# Water_Counter_Nathan_Amir.net
KiCad netlist of a schematic drawn in EasyEDA
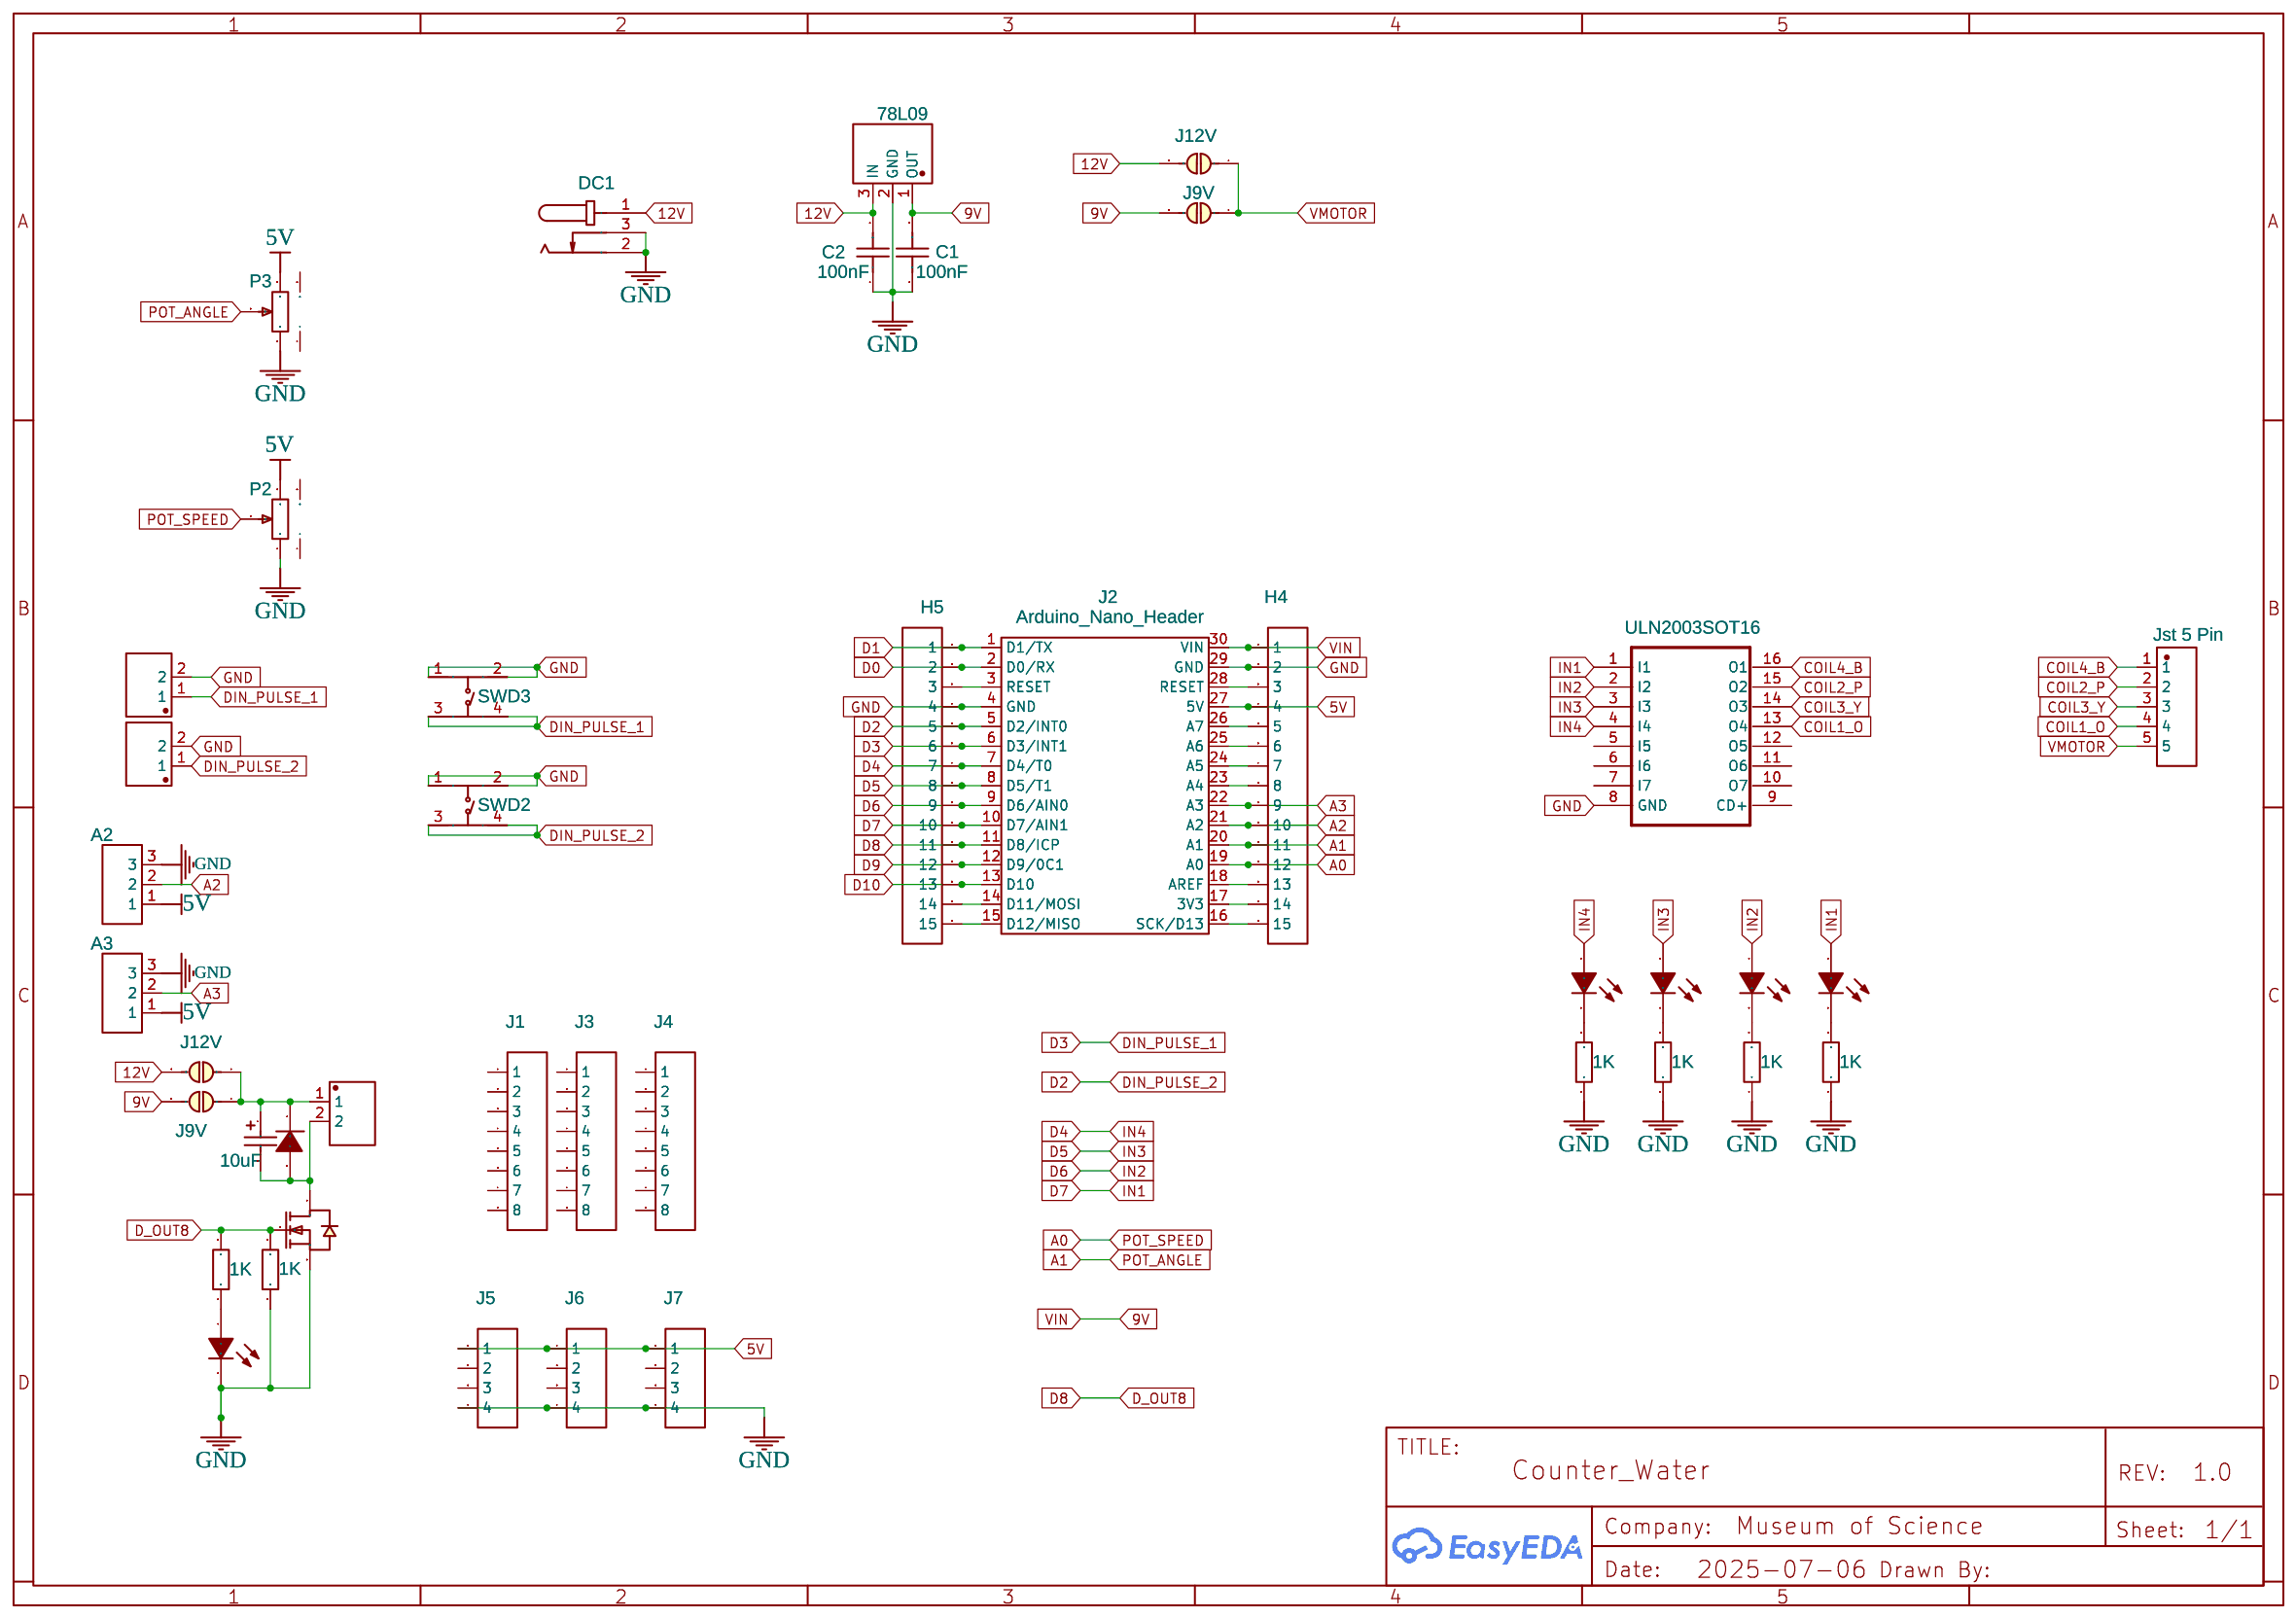
[diagram p0: schematic sheet]

(export (version "E")
  (design (tool "Eeschema 10.0.6"))
  (components
    (comp (ref "A2") (value "FK2510") (libsource (lib "") (part "kf2510_3A")))
    (comp (ref "A3") (value "FK2510") (libsource (lib "") (part "kf2510_3A")))
    (comp (ref "C1") (value "100nF") (libsource (lib "") (part "CC0603KRX7R9BB104")))
    (comp (ref "C2") (value "100nF") (libsource (lib "") (part "CC0603KRX7R9BB104")))
    (comp (ref "D2")
      (value "KF2510-2A")
      (fields (field (name "Manufacturer") "BOOMELE"))
      (libsource (lib "") (part "KF2510-2A"))
    )
    (comp (ref "D3")
      (value "KF2510-2A")
      (fields (field (name "Manufacturer") "BOOMELE"))
      (libsource (lib "") (part "KF2510-2A"))
    )
    (comp (ref "DC1")
      (value "DC")
      (fields (field (name "Manufacturer Part") "DC005-2.0MM") (field (name "Manufacturer") "SOFNG"))
      (libsource (lib "") (part "DC005-2.0MM"))
    )
    (comp (ref "ECM1") (value "10uF") (libsource (lib "") (part "TAJA106K016RNJ")))
    (comp (ref "ECON1")
      (value "D_OUT8")
      (fields (field (name "Manufacturer Part") "KF2510-2A") (field (name "Manufacturer") "BOOMELE"))
      (libsource (lib "") (part "KF2510-2A_1"))
    )
    (comp (ref "EDM1")
      (value "1N4007")
      (fields (field (name "Manufacturer Part") "1N4007F") (field (name "Manufacturer") "SK"))
      (libsource (lib "") (part "1N4007F"))
    )
    (comp (ref "ELD1")
      (value "LED")
      (fields
        (field (name "Manufacturer Part") "19-217/BHC-ZL1M2RY/3T")
        (field (name "Manufacturer") "EVERLIGHT")
      )
      (libsource (lib "") (part "19-217/BHC-ZL1M2RY/3T"))
    )
    (comp (ref "ELD2")
      (value "LED")
      (fields
        (field (name "Manufacturer Part") "19-217/BHC-ZL1M2RY/3T")
        (field (name "Manufacturer") "EVERLIGHT")
      )
      (libsource (lib "") (part "19-217/BHC-ZL1M2RY/3T"))
    )
    (comp (ref "ELD3")
      (value "LED")
      (fields
        (field (name "Manufacturer Part") "19-217/BHC-ZL1M2RY/3T")
        (field (name "Manufacturer") "EVERLIGHT")
      )
      (libsource (lib "") (part "19-217/BHC-ZL1M2RY/3T"))
    )
    (comp (ref "ELD4")
      (value "LED")
      (fields
        (field (name "Manufacturer Part") "19-217/BHC-ZL1M2RY/3T")
        (field (name "Manufacturer") "EVERLIGHT")
      )
      (libsource (lib "") (part "19-217/BHC-ZL1M2RY/3T"))
    )
    (comp (ref "ELD5")
      (value "LED")
      (fields
        (field (name "Manufacturer Part") "19-217/BHC-ZL1M2RY/3T")
        (field (name "Manufacturer") "EVERLIGHT")
      )
      (libsource (lib "") (part "19-217/BHC-ZL1M2RY/3T"))
    )
    (comp (ref "EQ1")
      (value "Q")
      (fields (field (name "Manufacturer Part") "AO3400") (field (name "Manufacturer") "ElecSuper(静芯微）"))
      (libsource (lib "") (part "JSM2302"))
    )
    (comp (ref "ERG1")
      (value "1K")
      (fields (field (name "Manufacturer Part") "0603WAF1001T5E") (field (name "Manufacturer") "UniOhm"))
      (libsource (lib "") (part "0603WAF1001T5E_1"))
    )
    (comp (ref "ERL1")
      (value "1K")
      (fields (field (name "Manufacturer Part") "0603WAF1001T5E") (field (name "Manufacturer") "UniOhm"))
      (libsource (lib "") (part "0603WAF1001T5E"))
    )
    (comp (ref "ERL2")
      (value "1K")
      (fields (field (name "Manufacturer Part") "0603WAF1001T5E") (field (name "Manufacturer") "UniOhm"))
      (libsource (lib "") (part "0603WAF1001T5E"))
    )
    (comp (ref "ERL3")
      (value "1K")
      (fields (field (name "Manufacturer Part") "0603WAF1001T5E") (field (name "Manufacturer") "UniOhm"))
      (libsource (lib "") (part "0603WAF1001T5E"))
    )
    (comp (ref "ERL4")
      (value "1K")
      (fields (field (name "Manufacturer Part") "0603WAF1001T5E") (field (name "Manufacturer") "UniOhm"))
      (libsource (lib "") (part "0603WAF1001T5E"))
    )
    (comp (ref "ERL5")
      (value "1K")
      (fields (field (name "Manufacturer Part") "0603WAF1001T5E") (field (name "Manufacturer") "UniOhm"))
      (libsource (lib "") (part "0603WAF1001T5E"))
    )
    (comp (ref "H4") (value "HDR-F-2.54_1x15") (libsource (lib "") (part "HDR-F-2.54_1x15_1")))
    (comp (ref "H5") (value "HDR-F-2.54_1x15") (libsource (lib "") (part "HDR-F-2.54_1x15")))
    (comp (ref "IC1") (value "ULN2003SOT16") (libsource (lib "") (part "ULN2003SOT16")))
    (comp (ref "J1")
      (value "HDR-M-2.54_1x8")
      (fields (field (name "BOM_Supplier Part") "C190820"))
      (libsource (lib "") (part "HDR-M-2.54_1x8"))
    )
    (comp (ref "J2") (value "Arduino_Nano_Header") (libsource (lib "") (part "Arduino_Nano_Header")))
    (comp (ref "J3")
      (value "HDR-M-2.54_1x8")
      (fields (field (name "BOM_Supplier Part") "C190820"))
      (libsource (lib "") (part "HDR-M-2.54_1x8"))
    )
    (comp (ref "J4")
      (value "HDR-M-2.54_1x8")
      (fields (field (name "BOM_Supplier Part") "C190820"))
      (libsource (lib "") (part "HDR-M-2.54_1x8"))
    )
    (comp (ref "J5")
      (value "HDR-M-2.54_1x4")
      (fields (field (name "BOM_Supplier Part") "C124378"))
      (libsource (lib "") (part "HDR-M-2.54_1x4"))
    )
    (comp (ref "J5V_2") (value "J9V") (libsource (lib "") (part "JUMPER-SMT_2")))
    (comp (ref "J6")
      (value "HDR-M-2.54_1x4")
      (fields (field (name "BOM_Supplier Part") "C124378"))
      (libsource (lib "") (part "HDR-M-2.54_1x4"))
    )
    (comp (ref "J7")
      (value "HDR-M-2.54_1x4")
      (fields (field (name "BOM_Supplier Part") "C124378"))
      (libsource (lib "") (part "HDR-M-2.54_1x4"))
    )
    (comp (ref "J9V_1") (value "J9V") (libsource (lib "") (part "JUMPER-SMT_2_2")))
    (comp (ref "J12V_1") (value "J12V") (libsource (lib "") (part "JUMPER-SMT_2_1")))
    (comp (ref "J12V_2") (value "J12V") (libsource (lib "") (part "JUMPER-SMT_2_1")))
    (comp (ref "P2") (value "长柄旋转电位器") (libsource (lib "") (part "长柄旋转电位器")))
    (comp (ref "P3") (value "长柄旋转电位器") (libsource (lib "") (part "长柄旋转电位器")))
    (comp (ref "SWD2")
      (value "TC-6610-7-160G")
      (fields (field (name "Manufacturer") "HCTL(华灿天禄)"))
      (libsource (lib "") (part "TC-6610-7-160G"))
    )
    (comp (ref "SWD3")
      (value "TC-6610-7-160G")
      (fields (field (name "Manufacturer") "HCTL(华灿天禄)"))
      (libsource (lib "") (part "TC-6610-7-160G"))
    )
    (comp (ref "U1")
      (value "78L09")
      (fields (field (name "Manufacturer") "CBI(创基)"))
      (libsource (lib "") (part "78L09U 78L09"))
    )
    (comp (ref "U2")
      (value "Jst 5 Pin")
      (fields (field (name "Manufacturer") "Vicky"))
      (libsource (lib "") (part "Jst 5 Pin"))
    )
  )
  (nets
    (net (code "1") (name "5V") (class "Default")
      (node (ref "A2") (pin "1") (pinfunction "1_1") (pintype "unspecified"))
      (node (ref "A3") (pin "1") (pinfunction "1_1") (pintype "unspecified"))
      (node (ref "H4") (pin "4") (pinfunction "4_4") (pintype "unspecified"))
      (node (ref "J2") (pin "27") (pinfunction "5V_27") (pintype "unspecified"))
      (node (ref "J5") (pin "1") (pinfunction "1_1") (pintype "unspecified"))
      (node (ref "J6") (pin "1") (pinfunction "1_1") (pintype "unspecified"))
      (node (ref "J7") (pin "1") (pinfunction "1_1") (pintype "unspecified"))
      (node (ref "P2") (pin "3") (pinfunction "3_3") (pintype "input"))
      (node (ref "P3") (pin "3") (pinfunction "3_3") (pintype "input"))
    )
    (net (code "2") (name "9V") (class "Default")
      (node (ref "C1") (pin "2") (pinfunction "2_2") (pintype "unspecified"))
      (node (ref "H4") (pin "1") (pinfunction "1_1") (pintype "unspecified"))
      (node (ref "J2") (pin "30") (pinfunction "VIN_30") (pintype "unspecified"))
      (node (ref "J5V_2") (pin "2") (pinfunction "2_2") (pintype "bidirectional"))
      (node (ref "J9V_1") (pin "2") (pinfunction "2_2") (pintype "bidirectional"))
      (node (ref "U1") (pin "1") (pinfunction "OUT_1") (pintype "unspecified"))
    )
    (net (code "3") (name "12V") (class "Default")
      (node (ref "C2") (pin "2") (pinfunction "2_2") (pintype "unspecified"))
      (node (ref "DC1") (pin "1") (pinfunction "1_1") (pintype "unspecified"))
      (node (ref "J12V_1") (pin "2") (pinfunction "2_2") (pintype "bidirectional"))
      (node (ref "J12V_2") (pin "2") (pinfunction "2_2") (pintype "bidirectional"))
      (node (ref "U1") (pin "3") (pinfunction "IN_3") (pintype "unspecified"))
    )
    (net (code "4") (name "A0") (class "Default")
      (node (ref "H4") (pin "12") (pinfunction "12_12") (pintype "unspecified"))
      (node (ref "J2") (pin "19") (pinfunction "A0_19") (pintype "unspecified"))
      (node (ref "P2") (pin "2") (pinfunction "2_2") (pintype "input"))
    )
    (net (code "5") (name "A1") (class "Default")
      (node (ref "H4") (pin "11") (pinfunction "11_11") (pintype "unspecified"))
      (node (ref "J2") (pin "20") (pinfunction "A1_20") (pintype "unspecified"))
      (node (ref "P3") (pin "2") (pinfunction "2_2") (pintype "input"))
    )
    (net (code "6") (name "A2") (class "Default")
      (node (ref "A2") (pin "2") (pinfunction "2_2") (pintype "unspecified"))
      (node (ref "H4") (pin "10") (pinfunction "10_10") (pintype "unspecified"))
      (node (ref "J2") (pin "21") (pinfunction "A2_21") (pintype "unspecified"))
    )
    (net (code "7") (name "A3") (class "Default")
      (node (ref "A3") (pin "2") (pinfunction "2_2") (pintype "unspecified"))
      (node (ref "H4") (pin "9") (pinfunction "9_9") (pintype "unspecified"))
      (node (ref "J2") (pin "22") (pinfunction "A3_22") (pintype "unspecified"))
    )
    (net (code "8") (name "COIL1_O") (class "Default")
      (node (ref "IC1") (pin "13") (pinfunction "O4_13") (pintype "bidirectional"))
      (node (ref "U2") (pin "4") (pinfunction "4_4") (pintype "unspecified"))
    )
    (net (code "9") (name "COIL2_P") (class "Default")
      (node (ref "IC1") (pin "15") (pinfunction "O2_15") (pintype "bidirectional"))
      (node (ref "U2") (pin "2") (pinfunction "2_2") (pintype "unspecified"))
    )
    (net (code "10") (name "COIL3_Y") (class "Default")
      (node (ref "IC1") (pin "14") (pinfunction "O3_14") (pintype "bidirectional"))
      (node (ref "U2") (pin "3") (pinfunction "3_3") (pintype "unspecified"))
    )
    (net (code "11") (name "COIL4_B") (class "Default")
      (node (ref "IC1") (pin "16") (pinfunction "O1_16") (pintype "bidirectional"))
      (node (ref "U2") (pin "1") (pinfunction "1_1") (pintype "unspecified"))
    )
    (net (code "12") (name "D0") (class "Default")
      (node (ref "H5") (pin "2") (pinfunction "2_2") (pintype "unspecified"))
      (node (ref "J2") (pin "2") (pinfunction "D0/RX_2") (pintype "unspecified"))
    )
    (net (code "13") (name "D1") (class "Default")
      (node (ref "H5") (pin "1") (pinfunction "1_1") (pintype "unspecified"))
      (node (ref "J2") (pin "1") (pinfunction "D1/TX_1") (pintype "unspecified"))
    )
    (net (code "14") (name "D2") (class "Default")
      (node (ref "D2") (pin "1") (pinfunction "1_1") (pintype "unspecified"))
      (node (ref "H5") (pin "5") (pinfunction "5_5") (pintype "unspecified"))
      (node (ref "J2") (pin "5") (pinfunction "D2/INT0_5") (pintype "unspecified"))
      (node (ref "SWD2") (pin "3") (pinfunction "3_3") (pintype "unspecified"))
      (node (ref "SWD2") (pin "4") (pinfunction "4_4") (pintype "unspecified"))
    )
    (net (code "15") (name "D3") (class "Default")
      (node (ref "D3") (pin "1") (pinfunction "1_1") (pintype "unspecified"))
      (node (ref "H5") (pin "6") (pinfunction "6_6") (pintype "unspecified"))
      (node (ref "J2") (pin "6") (pinfunction "D3/INT1_6") (pintype "unspecified"))
      (node (ref "SWD3") (pin "3") (pinfunction "3_3") (pintype "unspecified"))
      (node (ref "SWD3") (pin "4") (pinfunction "4_4") (pintype "unspecified"))
    )
    (net (code "16") (name "D4") (class "Default")
      (node (ref "ELD1") (pin "1") (pinfunction "A_1") (pintype "input"))
      (node (ref "H5") (pin "7") (pinfunction "7_7") (pintype "unspecified"))
      (node (ref "IC1") (pin "4") (pinfunction "I4_4") (pintype "bidirectional"))
      (node (ref "J2") (pin "7") (pinfunction "D4/T0_7") (pintype "unspecified"))
    )
    (net (code "17") (name "D5") (class "Default")
      (node (ref "ELD4") (pin "1") (pinfunction "A_1") (pintype "input"))
      (node (ref "H5") (pin "8") (pinfunction "8_8") (pintype "unspecified"))
      (node (ref "IC1") (pin "3") (pinfunction "I3_3") (pintype "bidirectional"))
      (node (ref "J2") (pin "8") (pinfunction "D5/T1_8") (pintype "unspecified"))
    )
    (net (code "18") (name "D6") (class "Default")
      (node (ref "ELD2") (pin "1") (pinfunction "A_1") (pintype "input"))
      (node (ref "H5") (pin "9") (pinfunction "9_9") (pintype "unspecified"))
      (node (ref "IC1") (pin "2") (pinfunction "I2_2") (pintype "bidirectional"))
      (node (ref "J2") (pin "9") (pinfunction "D6/AIN0_9") (pintype "unspecified"))
    )
    (net (code "19") (name "D7") (class "Default")
      (node (ref "ELD3") (pin "1") (pinfunction "A_1") (pintype "input"))
      (node (ref "H5") (pin "10") (pinfunction "10_10") (pintype "unspecified"))
      (node (ref "IC1") (pin "1") (pinfunction "I1_1") (pintype "bidirectional"))
      (node (ref "J2") (pin "10") (pinfunction "D7/AIN1_10") (pintype "unspecified"))
    )
    (net (code "20") (name "D8") (class "Default")
      (node (ref "EQ1") (pin "1") (pinfunction "G_1") (pintype "unspecified"))
      (node (ref "ERG1") (pin "2") (pinfunction "2_2") (pintype "input"))
      (node (ref "ERL5") (pin "2") (pinfunction "2_2") (pintype "input"))
      (node (ref "H5") (pin "11") (pinfunction "11_11") (pintype "unspecified"))
      (node (ref "J2") (pin "11") (pinfunction "D8/ICP_11") (pintype "unspecified"))
    )
    (net (code "21") (name "D9") (class "Default")
      (node (ref "H5") (pin "12") (pinfunction "12_12") (pintype "unspecified"))
      (node (ref "J2") (pin "12") (pinfunction "D9/0C1_12") (pintype "unspecified"))
    )
    (net (code "22") (name "D10") (class "Default")
      (node (ref "H5") (pin "13") (pinfunction "13_13") (pintype "unspecified"))
      (node (ref "J2") (pin "13") (pinfunction "D10_13") (pintype "unspecified"))
    )
    (net (code "23") (name "GND") (class "Default")
      (node (ref "A2") (pin "3") (pinfunction "3_3") (pintype "unspecified"))
      (node (ref "A3") (pin "3") (pinfunction "3_3") (pintype "unspecified"))
      (node (ref "C1") (pin "1") (pinfunction "1_1") (pintype "unspecified"))
      (node (ref "C2") (pin "1") (pinfunction "1_1") (pintype "unspecified"))
      (node (ref "D2") (pin "2") (pinfunction "2_2") (pintype "unspecified"))
      (node (ref "D3") (pin "2") (pinfunction "2_2") (pintype "unspecified"))
      (node (ref "DC1") (pin "2") (pinfunction "2_2") (pintype "unspecified"))
      (node (ref "DC1") (pin "3") (pinfunction "3_3") (pintype "unspecified"))
      (node (ref "ELD5") (pin "2") (pinfunction "C_2") (pintype "input"))
      (node (ref "EQ1") (pin "2") (pinfunction "S_2") (pintype "unspecified"))
      (node (ref "ERG1") (pin "1") (pinfunction "1_1") (pintype "input"))
      (node (ref "ERL1") (pin "1") (pinfunction "1_1") (pintype "input"))
      (node (ref "ERL2") (pin "1") (pinfunction "1_1") (pintype "input"))
      (node (ref "ERL3") (pin "1") (pinfunction "1_1") (pintype "input"))
      (node (ref "ERL4") (pin "1") (pinfunction "1_1") (pintype "input"))
      (node (ref "H4") (pin "2") (pinfunction "2_2") (pintype "unspecified"))
      (node (ref "H5") (pin "4") (pinfunction "4_4") (pintype "unspecified"))
      (node (ref "IC1") (pin "8") (pinfunction "GND_8") (pintype "bidirectional"))
      (node (ref "J2") (pin "29") (pinfunction "GND_29") (pintype "unspecified"))
      (node (ref "J2") (pin "4") (pinfunction "GND_4") (pintype "unspecified"))
      (node (ref "J5") (pin "4") (pinfunction "4_4") (pintype "unspecified"))
      (node (ref "J6") (pin "4") (pinfunction "4_4") (pintype "unspecified"))
      (node (ref "J7") (pin "4") (pinfunction "4_4") (pintype "unspecified"))
      (node (ref "P2") (pin "1") (pinfunction "1_1") (pintype "input"))
      (node (ref "P3") (pin "1") (pinfunction "1_1") (pintype "input"))
      (node (ref "SWD2") (pin "1") (pinfunction "1_1") (pintype "unspecified"))
      (node (ref "SWD2") (pin "2") (pinfunction "2_2") (pintype "unspecified"))
      (node (ref "SWD3") (pin "1") (pinfunction "1_1") (pintype "unspecified"))
      (node (ref "SWD3") (pin "2") (pinfunction "2_2") (pintype "unspecified"))
      (node (ref "U1") (pin "2") (pinfunction "GND_2") (pintype "unspecified"))
    )
    (net (code "24") (name "Net-(EDM1-A)") (class "Default")
      (node (ref "ECM1") (pin "2") (pinfunction "2_2") (pintype "input"))
      (node (ref "ECON1") (pin "2") (pinfunction "2_2") (pintype "unspecified"))
      (node (ref "EDM1") (pin "2") (pinfunction "A_2") (pintype "unspecified"))
      (node (ref "EQ1") (pin "3") (pinfunction "D_3") (pintype "unspecified"))
    )
    (net (code "25") (name "Net-(EDM1-C)") (class "Default")
      (node (ref "ECM1") (pin "1") (pinfunction "1_1") (pintype "input"))
      (node (ref "ECON1") (pin "1") (pinfunction "1_1") (pintype "unspecified"))
      (node (ref "EDM1") (pin "1") (pinfunction "C_1") (pintype "unspecified"))
      (node (ref "J12V_2") (pin "1") (pinfunction "1_1") (pintype "bidirectional"))
      (node (ref "J5V_2") (pin "1") (pinfunction "1_1") (pintype "bidirectional"))
    )
    (net (code "26") (name "Net-(ELD1-C)") (class "Default")
      (node (ref "ELD1") (pin "2") (pinfunction "C_2") (pintype "input"))
      (node (ref "ERL1") (pin "2") (pinfunction "2_2") (pintype "input"))
    )
    (net (code "27") (name "Net-(ELD2-C)") (class "Default")
      (node (ref "ELD2") (pin "2") (pinfunction "C_2") (pintype "input"))
      (node (ref "ERL2") (pin "2") (pinfunction "2_2") (pintype "input"))
    )
    (net (code "28") (name "Net-(ELD3-C)") (class "Default")
      (node (ref "ELD3") (pin "2") (pinfunction "C_2") (pintype "input"))
      (node (ref "ERL3") (pin "2") (pinfunction "2_2") (pintype "input"))
    )
    (net (code "29") (name "Net-(ELD4-C)") (class "Default")
      (node (ref "ELD4") (pin "2") (pinfunction "C_2") (pintype "input"))
      (node (ref "ERL4") (pin "2") (pinfunction "2_2") (pintype "input"))
    )
    (net (code "30") (name "Net-(ELD5-A)") (class "Default")
      (node (ref "ELD5") (pin "1") (pinfunction "A_1") (pintype "input"))
      (node (ref "ERL5") (pin "1") (pinfunction "1_1") (pintype "input"))
    )
    (net (code "31") (name "Net-(H4-Pad3)") (class "Default")
      (node (ref "H4") (pin "3") (pinfunction "3_3") (pintype "unspecified"))
      (node (ref "J2") (pin "28") (pinfunction "RESET_28") (pintype "unspecified"))
    )
    (net (code "32") (name "Net-(H5-Pad3)") (class "Default")
      (node (ref "H5") (pin "3") (pinfunction "3_3") (pintype "unspecified"))
      (node (ref "J2") (pin "3") (pinfunction "RESET_3") (pintype "unspecified"))
    )
    (net (code "33") (name "Net-(J2-3V3)") (class "Default")
      (node (ref "H4") (pin "14") (pinfunction "14_14") (pintype "unspecified"))
      (node (ref "J2") (pin "17") (pinfunction "3V3_17") (pintype "unspecified"))
    )
    (net (code "34") (name "Net-(J2-A4)") (class "Default")
      (node (ref "H4") (pin "8") (pinfunction "8_8") (pintype "unspecified"))
      (node (ref "J2") (pin "23") (pinfunction "A4_23") (pintype "unspecified"))
    )
    (net (code "35") (name "Net-(J2-A5)") (class "Default")
      (node (ref "H4") (pin "7") (pinfunction "7_7") (pintype "unspecified"))
      (node (ref "J2") (pin "24") (pinfunction "A5_24") (pintype "unspecified"))
    )
    (net (code "36") (name "Net-(J2-A6)") (class "Default")
      (node (ref "H4") (pin "6") (pinfunction "6_6") (pintype "unspecified"))
      (node (ref "J2") (pin "25") (pinfunction "A6_25") (pintype "unspecified"))
    )
    (net (code "37") (name "Net-(J2-A7)") (class "Default")
      (node (ref "H4") (pin "5") (pinfunction "5_5") (pintype "unspecified"))
      (node (ref "J2") (pin "26") (pinfunction "A7_26") (pintype "unspecified"))
    )
    (net (code "38") (name "Net-(J2-AREF)") (class "Default")
      (node (ref "H4") (pin "13") (pinfunction "13_13") (pintype "unspecified"))
      (node (ref "J2") (pin "18") (pinfunction "AREF_18") (pintype "unspecified"))
    )
    (net (code "39") (name "Net-(J2-D11{slash}MOSI)") (class "Default")
      (node (ref "H5") (pin "14") (pinfunction "14_14") (pintype "unspecified"))
      (node (ref "J2") (pin "14") (pinfunction "D11/MOSI_14") (pintype "unspecified"))
    )
    (net (code "40") (name "Net-(J2-D12{slash}MISO)") (class "Default")
      (node (ref "H5") (pin "15") (pinfunction "15_15") (pintype "unspecified"))
      (node (ref "J2") (pin "15") (pinfunction "D12/MISO_15") (pintype "unspecified"))
    )
    (net (code "41") (name "Net-(J2-SCK{slash}D13)") (class "Default")
      (node (ref "H4") (pin "15") (pinfunction "15_15") (pintype "unspecified"))
      (node (ref "J2") (pin "16") (pinfunction "SCK/D13_16") (pintype "unspecified"))
    )
    (net (code "42") (name "VMOTOR") (class "Default")
      (node (ref "J12V_1") (pin "1") (pinfunction "1_1") (pintype "bidirectional"))
      (node (ref "J9V_1") (pin "1") (pinfunction "1_1") (pintype "bidirectional"))
      (node (ref "U2") (pin "5") (pinfunction "5_5") (pintype "unspecified"))
    )
    (net (code "43") (name "unconnected-(IC1-CD+-Pad9)") (class "Default")
      (node (ref "IC1") (pin "9") (pinfunction "CD+_9") (pintype "bidirectional"))
    )
    (net (code "44") (name "unconnected-(IC1-I5-Pad5)") (class "Default")
      (node (ref "IC1") (pin "5") (pinfunction "I5_5") (pintype "bidirectional"))
    )
    (net (code "45") (name "unconnected-(IC1-I6-Pad6)") (class "Default")
      (node (ref "IC1") (pin "6") (pinfunction "I6_6") (pintype "bidirectional"))
    )
    (net (code "46") (name "unconnected-(IC1-I7-Pad7)") (class "Default")
      (node (ref "IC1") (pin "7") (pinfunction "I7_7") (pintype "bidirectional"))
    )
    (net (code "47") (name "unconnected-(IC1-O5-Pad12)") (class "Default")
      (node (ref "IC1") (pin "12") (pinfunction "O5_12") (pintype "bidirectional"))
    )
    (net (code "48") (name "unconnected-(IC1-O6-Pad11)") (class "Default")
      (node (ref "IC1") (pin "11") (pinfunction "O6_11") (pintype "bidirectional"))
    )
    (net (code "49") (name "unconnected-(IC1-O7-Pad10)") (class "Default")
      (node (ref "IC1") (pin "10") (pinfunction "O7_10") (pintype "bidirectional"))
    )
    (net (code "50") (name "unconnected-(J1-Pad1)") (class "Default")
      (node (ref "J1") (pin "1") (pinfunction "1_1") (pintype "unspecified"))
    )
    (net (code "51") (name "unconnected-(J1-Pad2)") (class "Default")
      (node (ref "J1") (pin "2") (pinfunction "2_2") (pintype "unspecified"))
    )
    (net (code "52") (name "unconnected-(J1-Pad3)") (class "Default")
      (node (ref "J1") (pin "3") (pinfunction "3_3") (pintype "unspecified"))
    )
    (net (code "53") (name "unconnected-(J1-Pad4)") (class "Default")
      (node (ref "J1") (pin "4") (pinfunction "4_4") (pintype "unspecified"))
    )
    (net (code "54") (name "unconnected-(J1-Pad5)") (class "Default")
      (node (ref "J1") (pin "5") (pinfunction "5_5") (pintype "unspecified"))
    )
    (net (code "55") (name "unconnected-(J1-Pad6)") (class "Default")
      (node (ref "J1") (pin "6") (pinfunction "6_6") (pintype "unspecified"))
    )
    (net (code "56") (name "unconnected-(J1-Pad7)") (class "Default")
      (node (ref "J1") (pin "7") (pinfunction "7_7") (pintype "unspecified"))
    )
    (net (code "57") (name "unconnected-(J1-Pad8)") (class "Default")
      (node (ref "J1") (pin "8") (pinfunction "8_8") (pintype "unspecified"))
    )
    (net (code "58") (name "unconnected-(J3-Pad1)") (class "Default")
      (node (ref "J3") (pin "1") (pinfunction "1_1") (pintype "unspecified"))
    )
    (net (code "59") (name "unconnected-(J3-Pad2)") (class "Default")
      (node (ref "J3") (pin "2") (pinfunction "2_2") (pintype "unspecified"))
    )
    (net (code "60") (name "unconnected-(J3-Pad3)") (class "Default")
      (node (ref "J3") (pin "3") (pinfunction "3_3") (pintype "unspecified"))
    )
    (net (code "61") (name "unconnected-(J3-Pad4)") (class "Default")
      (node (ref "J3") (pin "4") (pinfunction "4_4") (pintype "unspecified"))
    )
    (net (code "62") (name "unconnected-(J3-Pad5)") (class "Default")
      (node (ref "J3") (pin "5") (pinfunction "5_5") (pintype "unspecified"))
    )
    (net (code "63") (name "unconnected-(J3-Pad6)") (class "Default")
      (node (ref "J3") (pin "6") (pinfunction "6_6") (pintype "unspecified"))
    )
    (net (code "64") (name "unconnected-(J3-Pad7)") (class "Default")
      (node (ref "J3") (pin "7") (pinfunction "7_7") (pintype "unspecified"))
    )
    (net (code "65") (name "unconnected-(J3-Pad8)") (class "Default")
      (node (ref "J3") (pin "8") (pinfunction "8_8") (pintype "unspecified"))
    )
    (net (code "66") (name "unconnected-(J4-Pad1)") (class "Default")
      (node (ref "J4") (pin "1") (pinfunction "1_1") (pintype "unspecified"))
    )
    (net (code "67") (name "unconnected-(J4-Pad2)") (class "Default")
      (node (ref "J4") (pin "2") (pinfunction "2_2") (pintype "unspecified"))
    )
    (net (code "68") (name "unconnected-(J4-Pad3)") (class "Default")
      (node (ref "J4") (pin "3") (pinfunction "3_3") (pintype "unspecified"))
    )
    (net (code "69") (name "unconnected-(J4-Pad4)") (class "Default")
      (node (ref "J4") (pin "4") (pinfunction "4_4") (pintype "unspecified"))
    )
    (net (code "70") (name "unconnected-(J4-Pad5)") (class "Default")
      (node (ref "J4") (pin "5") (pinfunction "5_5") (pintype "unspecified"))
    )
    (net (code "71") (name "unconnected-(J4-Pad6)") (class "Default")
      (node (ref "J4") (pin "6") (pinfunction "6_6") (pintype "unspecified"))
    )
    (net (code "72") (name "unconnected-(J4-Pad7)") (class "Default")
      (node (ref "J4") (pin "7") (pinfunction "7_7") (pintype "unspecified"))
    )
    (net (code "73") (name "unconnected-(J4-Pad8)") (class "Default")
      (node (ref "J4") (pin "8") (pinfunction "8_8") (pintype "unspecified"))
    )
    (net (code "74") (name "unconnected-(J5-Pad2)") (class "Default")
      (node (ref "J5") (pin "2") (pinfunction "2_2") (pintype "unspecified"))
    )
    (net (code "75") (name "unconnected-(J5-Pad3)") (class "Default")
      (node (ref "J5") (pin "3") (pinfunction "3_3") (pintype "unspecified"))
    )
    (net (code "76") (name "unconnected-(J6-Pad2)") (class "Default")
      (node (ref "J6") (pin "2") (pinfunction "2_2") (pintype "unspecified"))
    )
    (net (code "77") (name "unconnected-(J6-Pad3)") (class "Default")
      (node (ref "J6") (pin "3") (pinfunction "3_3") (pintype "unspecified"))
    )
    (net (code "78") (name "unconnected-(J7-Pad2)") (class "Default")
      (node (ref "J7") (pin "2") (pinfunction "2_2") (pintype "unspecified"))
    )
    (net (code "79") (name "unconnected-(J7-Pad3)") (class "Default")
      (node (ref "J7") (pin "3") (pinfunction "3_3") (pintype "unspecified"))
    )
    (net (code "80") (name "unconnected-(P2-Pad4)") (class "Default")
      (node (ref "P2") (pin "4") (pinfunction "4_4") (pintype "input"))
    )
    (net (code "81") (name "unconnected-(P2-Pad5)") (class "Default")
      (node (ref "P2") (pin "5") (pinfunction "5_5") (pintype "input"))
    )
    (net (code "82") (name "unconnected-(P3-Pad4)") (class "Default")
      (node (ref "P3") (pin "4") (pinfunction "4_4") (pintype "input"))
    )
    (net (code "83") (name "unconnected-(P3-Pad5)") (class "Default")
      (node (ref "P3") (pin "5") (pinfunction "5_5") (pintype "input"))
    )
  )
)
